# preparedinstruments_0_bechemel_v12_KEYPA.net
KiCad netlist of a schematic drawn in EAGLE
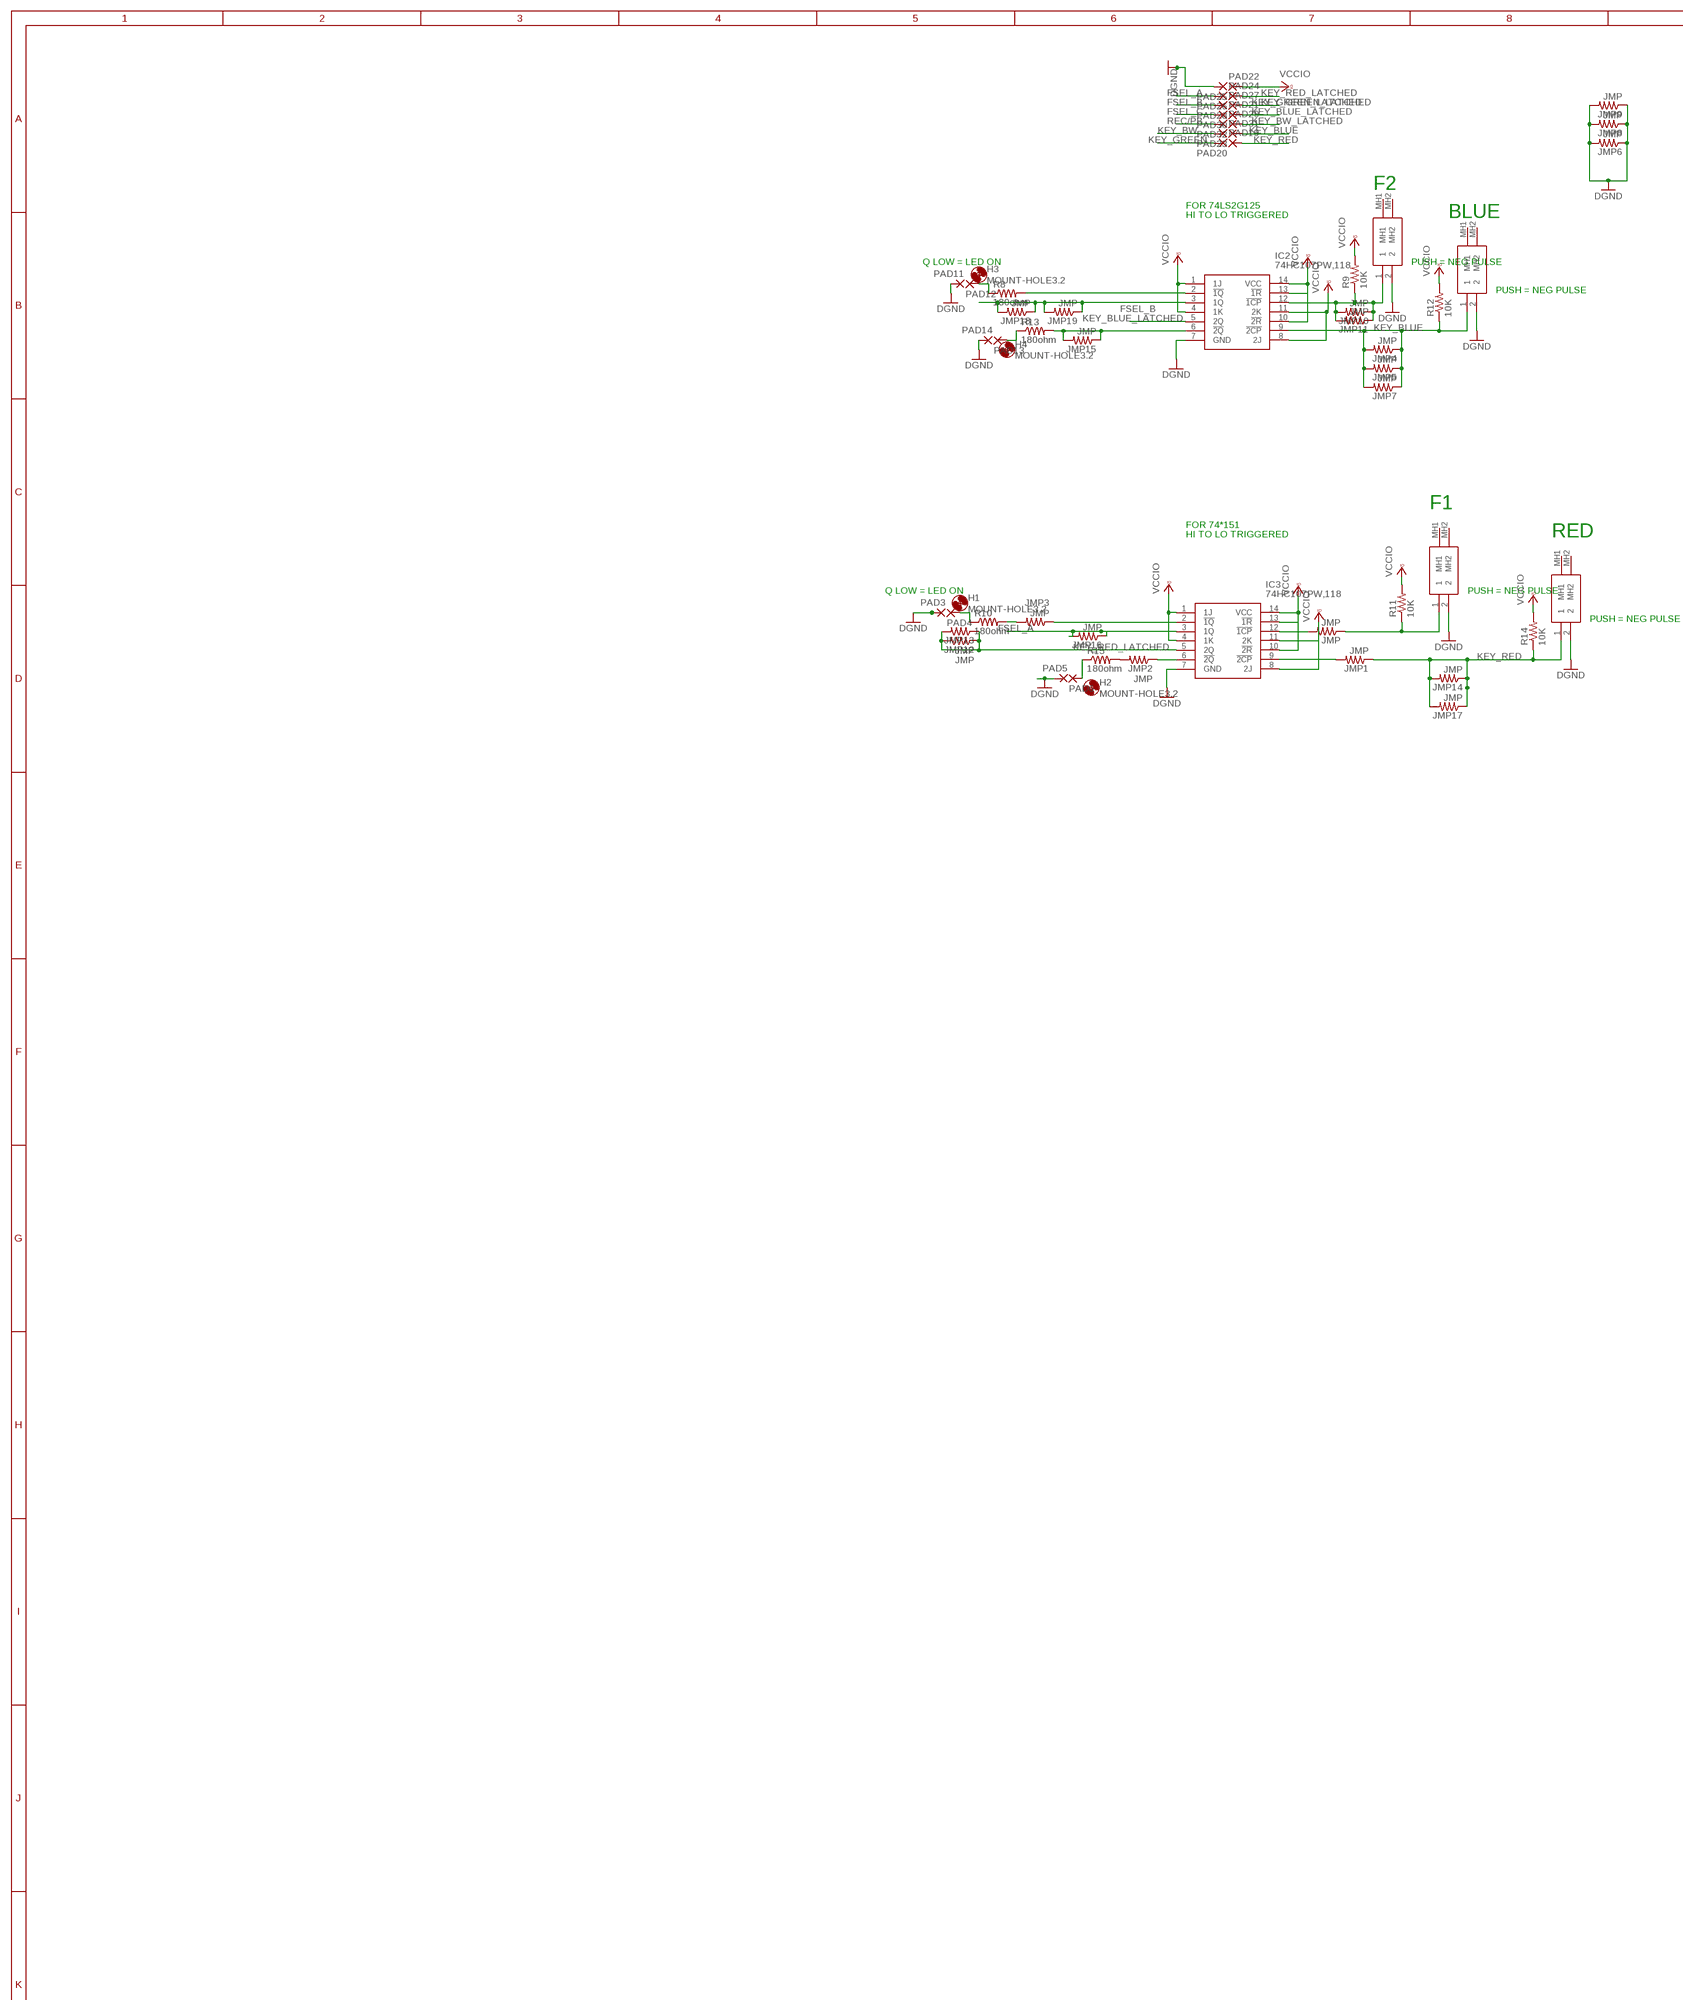
[diagram p0: schematic, sheet 1, part 1 of 3]
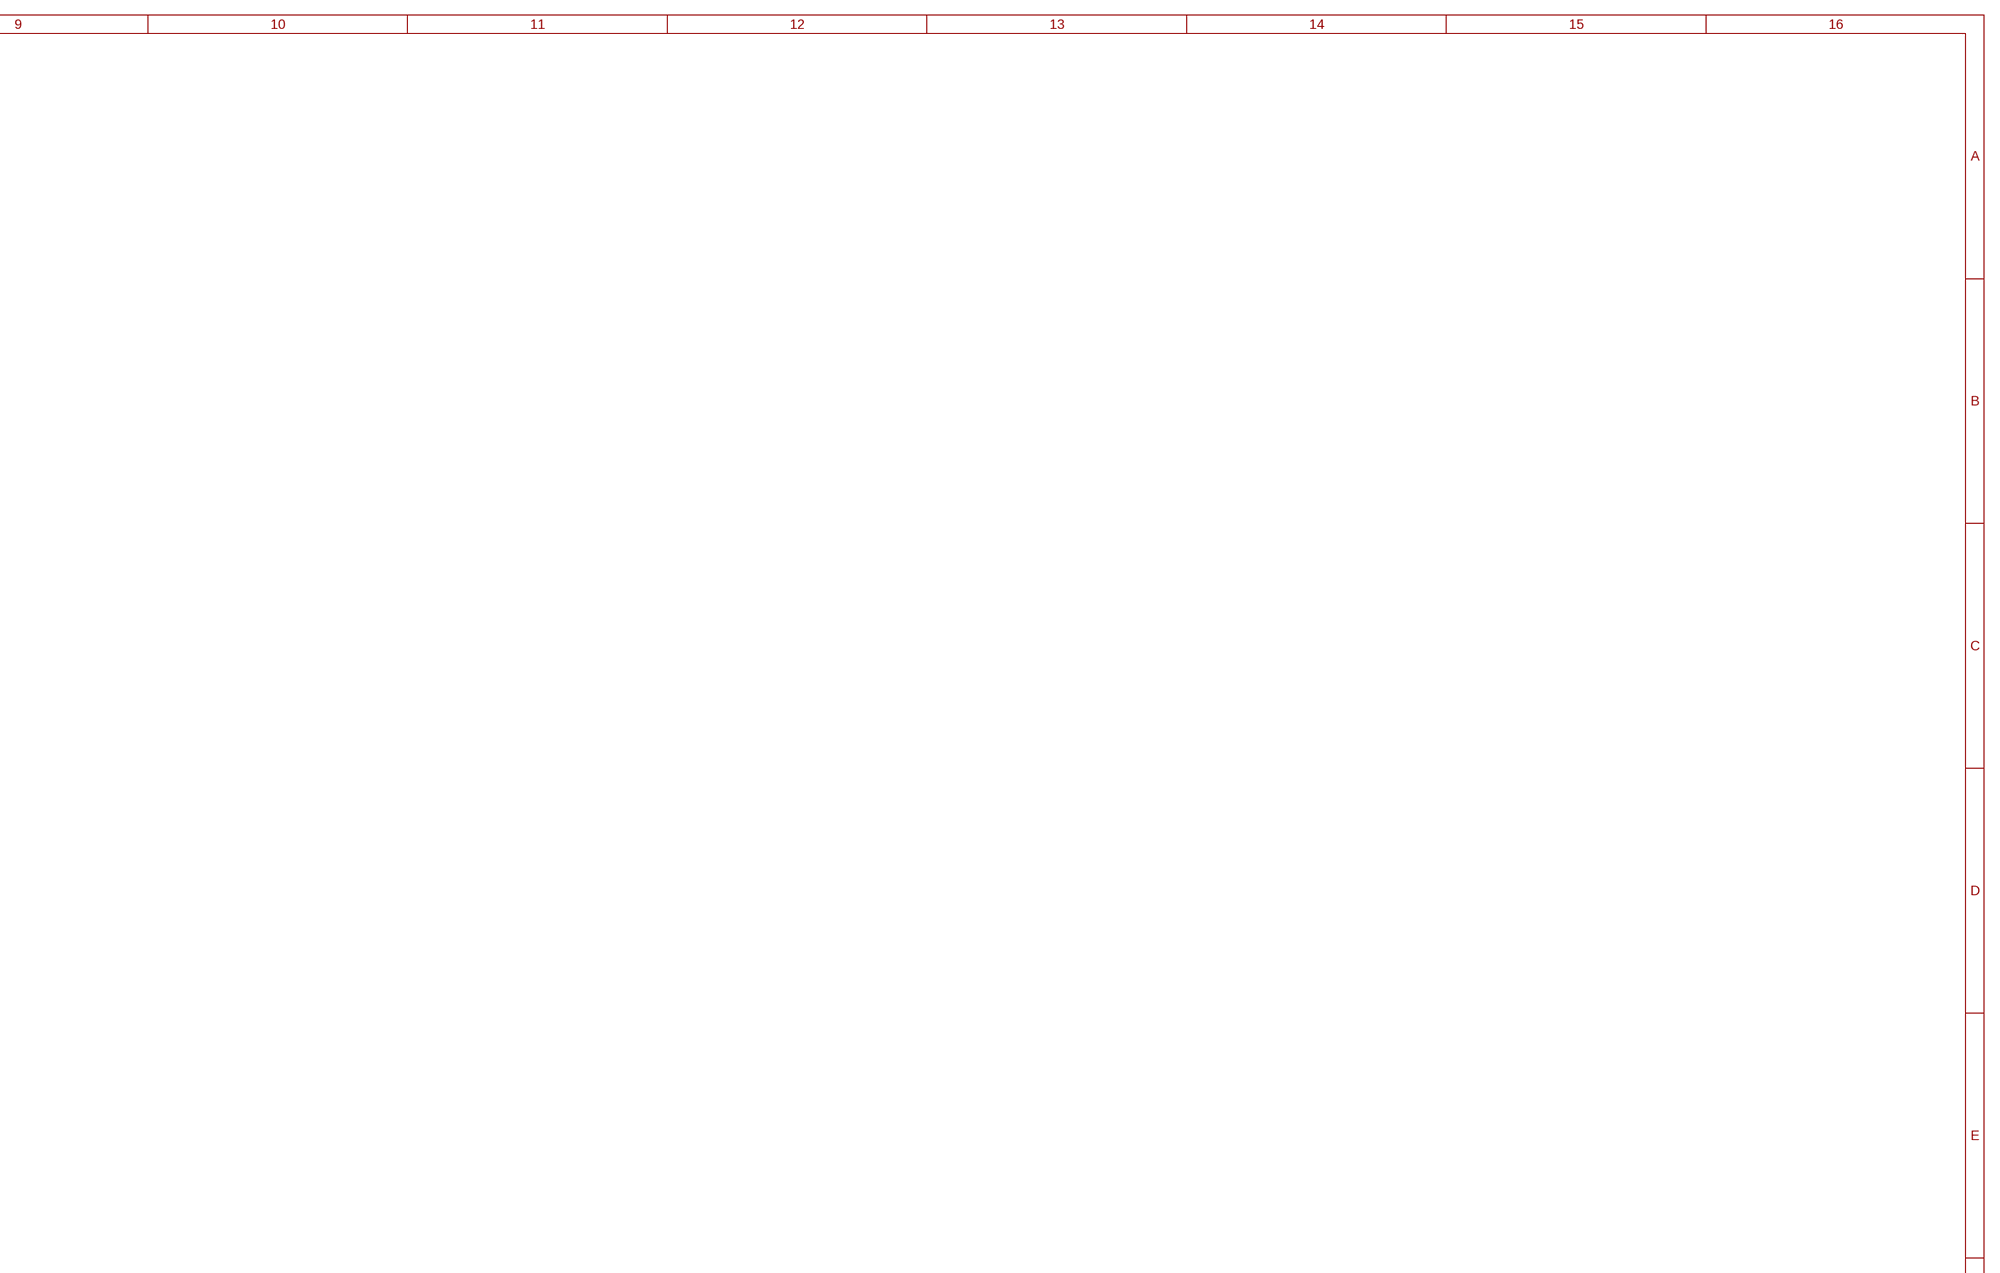
[diagram p1: schematic, sheet 1, part 2 of 3]
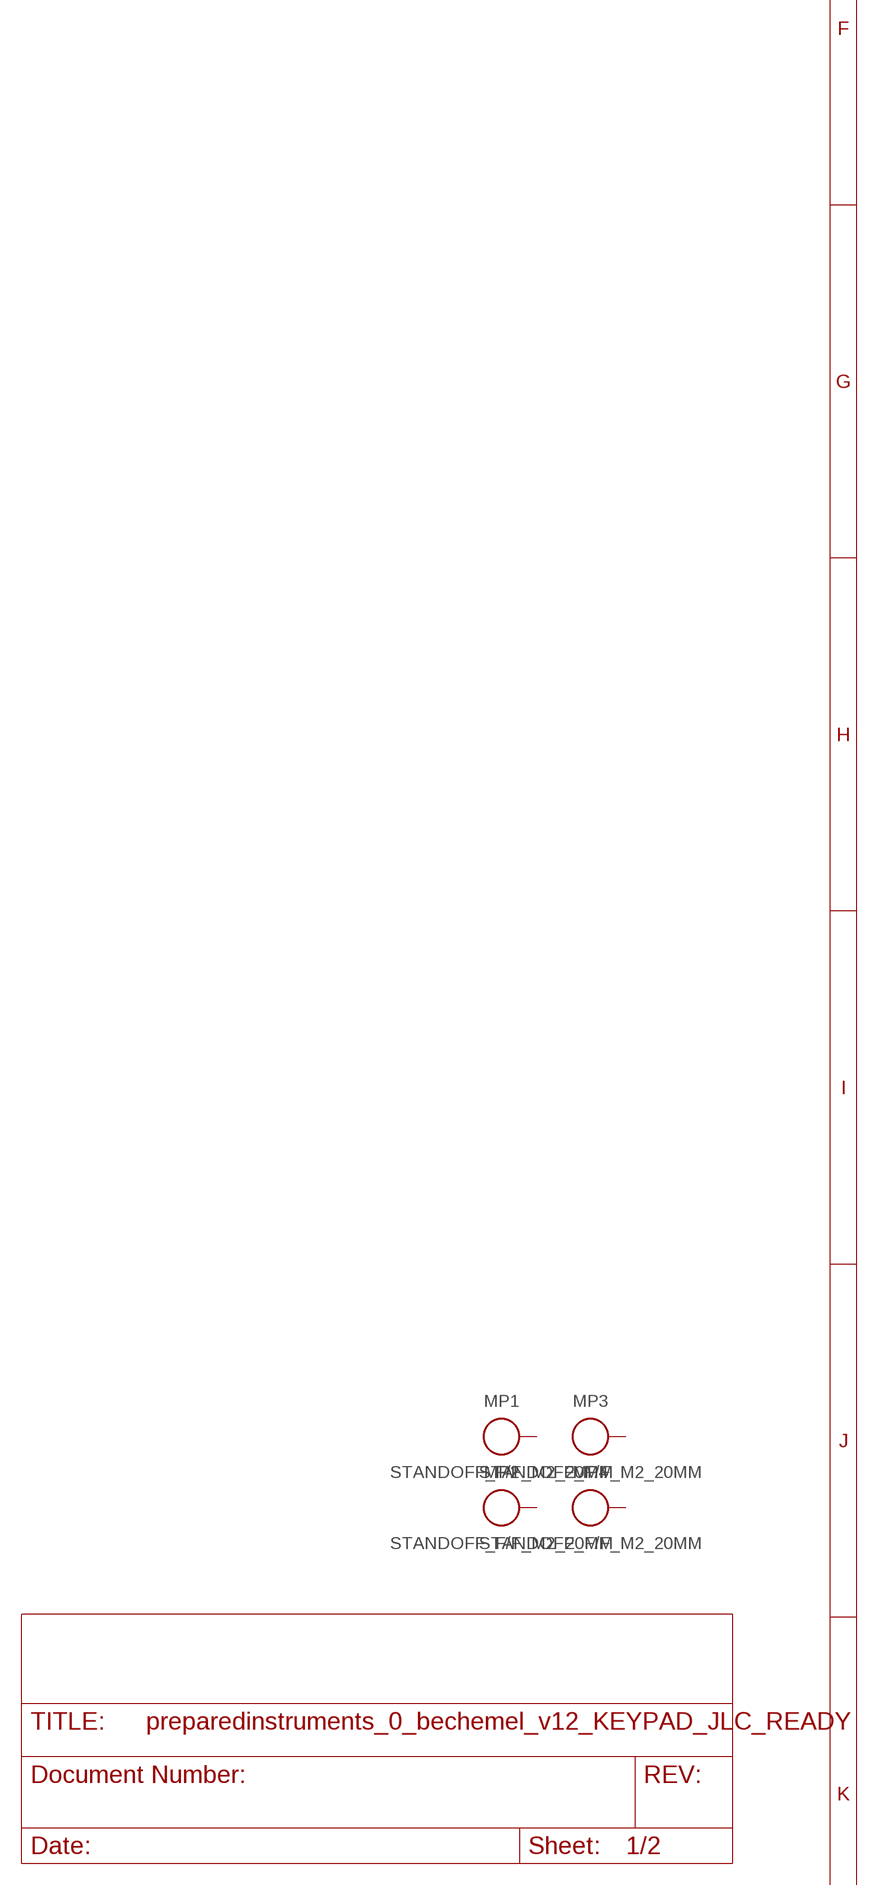
[diagram p2: schematic, sheet 1, part 3 of 3]
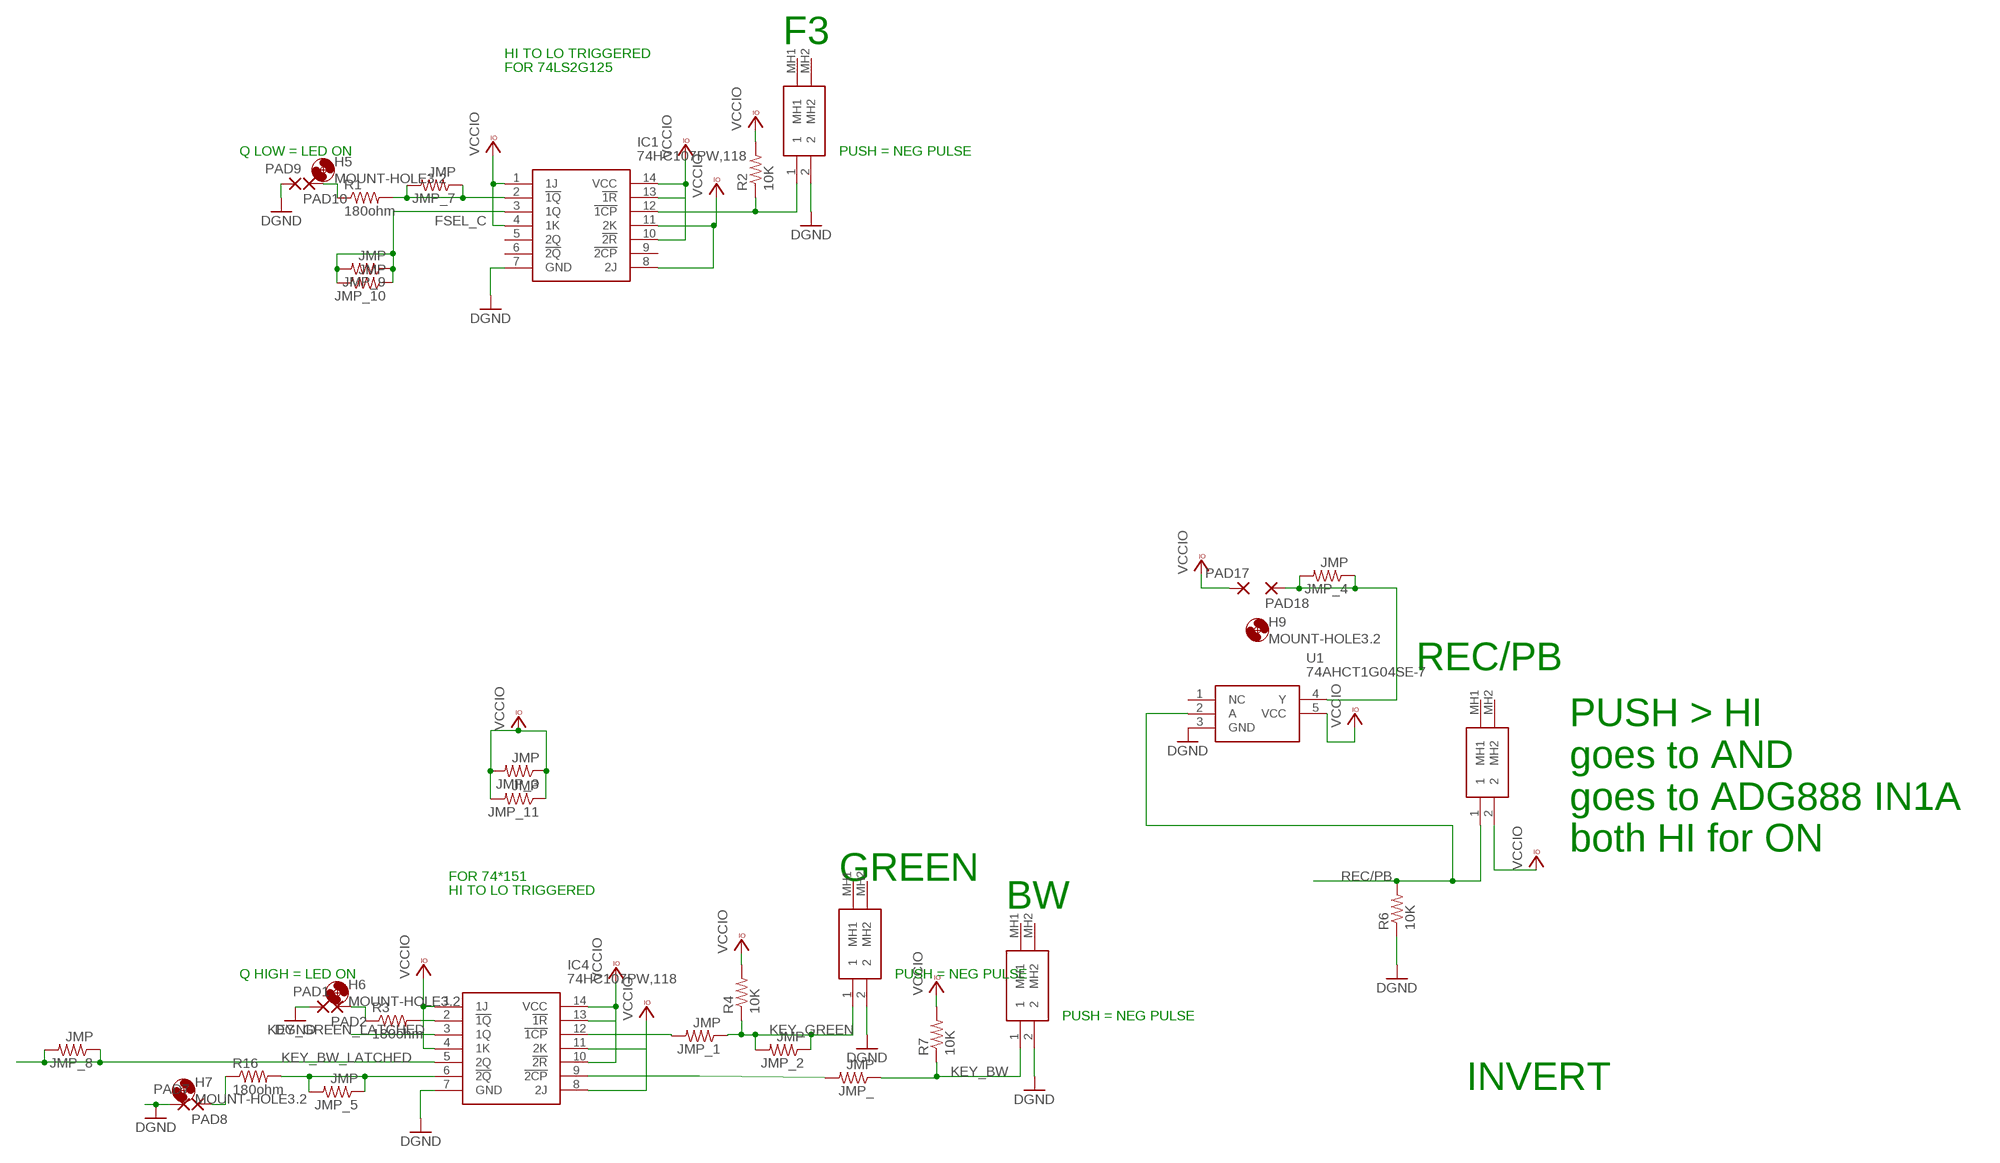
[diagram p3: schematic, sheet 2]

(export (version "E")
  (design (tool "Eeschema 10.0.6"))
  (components
    (comp (ref "H5")
      (value "MOUNT-HOLE3.2")
      (footprint "eagle-import:3,2")
      (libsource (lib "eagle-import") (part "MOUNT-HOLE3.2"))
    )
    (comp (ref "H6")
      (value "MOUNT-HOLE3.2")
      (footprint "eagle-import:3,2")
      (libsource (lib "eagle-import") (part "MOUNT-HOLE3.2"))
    )
    (comp (ref "H7")
      (value "MOUNT-HOLE3.2")
      (footprint "eagle-import:3,2")
      (libsource (lib "eagle-import") (part "MOUNT-HOLE3.2"))
    )
    (comp (ref "H9")
      (value "MOUNT-HOLE3.2")
      (footprint "eagle-import:3,2")
      (libsource (lib "eagle-import") (part "MOUNT-HOLE3.2"))
    )
    (comp (ref "IC1")
      (value "74HC107PW,118")
      (footprint "eagle-import:SOP65P640X110-14N")
      (fields (field (name "MOUSER_PART_NUMBER") "771-HC107PW118"))
      (libsource (lib "eagle-import") (part "74HC107PW,118"))
    )
    (comp (ref "IC4")
      (value "74HC107PW,118")
      (footprint "eagle-import:SOP65P640X110-14N")
      (fields (field (name "MOUSER_PART_NUMBER") "771-HC107PW118"))
      (libsource (lib "eagle-import") (part "74HC107PW,118"))
    )
    (comp (ref "JMP_")
      (value "JMP")
      (footprint "eagle-import:R0805")
      (libsource (lib "eagle-import") (part "R-US_R0805"))
    )
    (comp (ref "JMP_1")
      (value "JMP")
      (footprint "eagle-import:R0805")
      (libsource (lib "eagle-import") (part "R-US_R0805"))
    )
    (comp (ref "JMP_2")
      (value "JMP")
      (footprint "eagle-import:R0805")
      (libsource (lib "eagle-import") (part "R-US_R0805"))
    )
    (comp (ref "JMP_3")
      (value "JMP")
      (footprint "eagle-import:R0805")
      (libsource (lib "eagle-import") (part "R-US_R0805"))
    )
    (comp (ref "JMP_4")
      (value "JMP")
      (footprint "eagle-import:R0805")
      (libsource (lib "eagle-import") (part "R-US_R0805"))
    )
    (comp (ref "JMP_5")
      (value "JMP")
      (footprint "eagle-import:R0805")
      (libsource (lib "eagle-import") (part "R-US_R0805"))
    )
    (comp (ref "JMP_7")
      (value "JMP")
      (footprint "eagle-import:R0805")
      (libsource (lib "eagle-import") (part "R-US_R0805"))
    )
    (comp (ref "JMP_8")
      (value "JMP")
      (footprint "eagle-import:R0805")
      (libsource (lib "eagle-import") (part "R-US_R0805"))
    )
    (comp (ref "JMP_9")
      (value "JMP")
      (footprint "eagle-import:R0805")
      (libsource (lib "eagle-import") (part "R-US_R0805"))
    )
    (comp (ref "JMP_10")
      (value "JMP")
      (footprint "eagle-import:R0805")
      (libsource (lib "eagle-import") (part "R-US_R0805"))
    )
    (comp (ref "JMP_11")
      (value "JMP")
      (footprint "eagle-import:R0805")
      (libsource (lib "eagle-import") (part "R-US_R0805"))
    )
    (comp (ref "PAD1")
      (value "SMD2")
      (footprint "eagle-import:SMD1,27-2,54")
      (libsource (lib "eagle-import") (part "SMD2"))
    )
    (comp (ref "PAD2")
      (value "SMD2")
      (footprint "eagle-import:SMD1,27-2,54")
      (libsource (lib "eagle-import") (part "SMD2"))
    )
    (comp (ref "PAD7")
      (value "SMD2")
      (footprint "eagle-import:SMD1,27-2,54")
      (libsource (lib "eagle-import") (part "SMD2"))
    )
    (comp (ref "PAD8")
      (value "SMD2")
      (footprint "eagle-import:SMD1,27-2,54")
      (libsource (lib "eagle-import") (part "SMD2"))
    )
    (comp (ref "PAD9")
      (value "SMD2")
      (footprint "eagle-import:SMD1,27-2,54")
      (libsource (lib "eagle-import") (part "SMD2"))
    )
    (comp (ref "PAD10")
      (value "SMD2")
      (footprint "eagle-import:SMD1,27-2,54")
      (libsource (lib "eagle-import") (part "SMD2"))
    )
    (comp (ref "PAD17")
      (value "SMD2")
      (footprint "eagle-import:SMD1,27-2,54")
      (libsource (lib "eagle-import") (part "SMD2"))
    )
    (comp (ref "PAD18")
      (value "SMD2")
      (footprint "eagle-import:SMD1,27-2,54")
      (libsource (lib "eagle-import") (part "SMD2"))
    )
    (comp (ref "R1")
      (value "180ohm")
      (footprint "eagle-import:R0805")
      (libsource (lib "eagle-import") (part "R-US_R0805"))
    )
    (comp (ref "R2")
      (value "10K")
      (footprint "eagle-import:R0805")
      (libsource (lib "eagle-import") (part "R-US_R0805"))
    )
    (comp (ref "R3")
      (value "180ohm")
      (footprint "eagle-import:R0805")
      (libsource (lib "eagle-import") (part "R-US_R0805"))
    )
    (comp (ref "R4")
      (value "10K")
      (footprint "eagle-import:R0805")
      (libsource (lib "eagle-import") (part "R-US_R0805"))
    )
    (comp (ref "R6")
      (value "10K")
      (footprint "eagle-import:R0805")
      (libsource (lib "eagle-import") (part "R-US_R0805"))
    )
    (comp (ref "R7")
      (value "10K")
      (footprint "eagle-import:R0805")
      (libsource (lib "eagle-import") (part "R-US_R0805"))
    )
    (comp (ref "R16")
      (value "180ohm")
      (footprint "eagle-import:R0805")
      (libsource (lib "eagle-import") (part "R-US_R0805"))
    )
    (comp (ref "S1")
      (value "MX1A-11NW")
      (footprint "eagle-import:MX1A11NW")
      (fields (field (name "MOUSER_PART_NUMBER") "540-MX1A-11NW"))
      (libsource (lib "eagle-import") (part "MX1A-11NW"))
    )
    (comp (ref "S2")
      (value "MX1A-11NW")
      (footprint "eagle-import:MX1A11NW")
      (fields (field (name "MOUSER_PART_NUMBER") "540-MX1A-11NW"))
      (libsource (lib "eagle-import") (part "MX1A-11NW"))
    )
    (comp (ref "S4")
      (value "MX1A-11NW")
      (footprint "eagle-import:MX1A11NW")
      (fields (field (name "MOUSER_PART_NUMBER") "540-MX1A-11NW"))
      (libsource (lib "eagle-import") (part "MX1A-11NW"))
    )
    (comp (ref "S5")
      (value "MX1A-11NW")
      (footprint "eagle-import:MX1A11NW")
      (fields (field (name "MOUSER_PART_NUMBER") "540-MX1A-11NW"))
      (libsource (lib "eagle-import") (part "MX1A-11NW"))
    )
    (comp (ref "U1")
      (value "74AHCT1G04SE-7")
      (footprint "eagle-import:SOT65P210X110-5N")
      (fields (field (name "MOUSER_PART_NUMBER") "621-74AHCT1G04SE-7"))
      (libsource (lib "eagle-import") (part "74AHCT1G04SE-7"))
    )
    (comp (ref "H1")
      (value "MOUNT-HOLE3.2")
      (footprint "eagle-import:3,2")
      (libsource (lib "eagle-import") (part "MOUNT-HOLE3.2"))
    )
    (comp (ref "H2")
      (value "MOUNT-HOLE3.2")
      (footprint "eagle-import:3,2")
      (libsource (lib "eagle-import") (part "MOUNT-HOLE3.2"))
    )
    (comp (ref "H3")
      (value "MOUNT-HOLE3.2")
      (footprint "eagle-import:3,2")
      (libsource (lib "eagle-import") (part "MOUNT-HOLE3.2"))
    )
    (comp (ref "H4")
      (value "MOUNT-HOLE3.2")
      (footprint "eagle-import:3,2")
      (libsource (lib "eagle-import") (part "MOUNT-HOLE3.2"))
    )
    (comp (ref "IC2")
      (value "74HC107PW,118")
      (footprint "eagle-import:SOP65P640X110-14N")
      (fields (field (name "MOUSER_PART_NUMBER") "771-HC107PW118"))
      (libsource (lib "eagle-import") (part "74HC107PW,118"))
    )
    (comp (ref "IC3")
      (value "74HC107PW,118")
      (footprint "eagle-import:SOP65P640X110-14N")
      (fields (field (name "MOUSER_PART_NUMBER") "771-HC107PW118"))
      (libsource (lib "eagle-import") (part "74HC107PW,118"))
    )
    (comp (ref "JMP")
      (value "JMP")
      (footprint "eagle-import:R0805")
      (libsource (lib "eagle-import") (part "R-US_R0805"))
    )
    (comp (ref "JMP1")
      (value "JMP")
      (footprint "eagle-import:R0805")
      (libsource (lib "eagle-import") (part "R-US_R0805"))
    )
    (comp (ref "JMP2")
      (value "JMP")
      (footprint "eagle-import:R0805")
      (libsource (lib "eagle-import") (part "R-US_R0805"))
    )
    (comp (ref "JMP3")
      (value "JMP")
      (footprint "eagle-import:R0805")
      (libsource (lib "eagle-import") (part "R-US_R0805"))
    )
    (comp (ref "JMP4")
      (value "JMP")
      (footprint "eagle-import:R0805")
      (libsource (lib "eagle-import") (part "R-US_R0805"))
    )
    (comp (ref "JMP5")
      (value "JMP")
      (footprint "eagle-import:R0805")
      (libsource (lib "eagle-import") (part "R-US_R0805"))
    )
    (comp (ref "JMP6")
      (value "JMP")
      (footprint "eagle-import:R0805")
      (libsource (lib "eagle-import") (part "R-US_R0805"))
    )
    (comp (ref "JMP7")
      (value "JMP")
      (footprint "eagle-import:R0805")
      (libsource (lib "eagle-import") (part "R-US_R0805"))
    )
    (comp (ref "JMP8")
      (value "JMP")
      (footprint "eagle-import:R0805")
      (libsource (lib "eagle-import") (part "R-US_R0805"))
    )
    (comp (ref "JMP9")
      (value "JMP")
      (footprint "eagle-import:R0805")
      (libsource (lib "eagle-import") (part "R-US_R0805"))
    )
    (comp (ref "JMP10")
      (value "JMP")
      (footprint "eagle-import:R0805")
      (libsource (lib "eagle-import") (part "R-US_R0805"))
    )
    (comp (ref "JMP11")
      (value "JMP")
      (footprint "eagle-import:R0805")
      (libsource (lib "eagle-import") (part "R-US_R0805"))
    )
    (comp (ref "JMP12")
      (value "JMP")
      (footprint "eagle-import:R0805")
      (libsource (lib "eagle-import") (part "R-US_R0805"))
    )
    (comp (ref "JMP13")
      (value "JMP")
      (footprint "eagle-import:R0805")
      (libsource (lib "eagle-import") (part "R-US_R0805"))
    )
    (comp (ref "JMP14")
      (value "JMP")
      (footprint "eagle-import:R0805")
      (libsource (lib "eagle-import") (part "R-US_R0805"))
    )
    (comp (ref "JMP15")
      (value "JMP")
      (footprint "eagle-import:R0805")
      (libsource (lib "eagle-import") (part "R-US_R0805"))
    )
    (comp (ref "JMP16")
      (value "JMP")
      (footprint "eagle-import:R0805")
      (libsource (lib "eagle-import") (part "R-US_R0805"))
    )
    (comp (ref "JMP17")
      (value "JMP")
      (footprint "eagle-import:R0805")
      (libsource (lib "eagle-import") (part "R-US_R0805"))
    )
    (comp (ref "JMP18")
      (value "JMP")
      (footprint "eagle-import:R0805")
      (libsource (lib "eagle-import") (part "R-US_R0805"))
    )
    (comp (ref "JMP19")
      (value "JMP")
      (footprint "eagle-import:R0805")
      (libsource (lib "eagle-import") (part "R-US_R0805"))
    )
    (comp (ref "MP1")
      (value "STANDOFF_F/F_M2_20MM")
      (footprint "eagle-import:STANDOFF_HEX_FEMALE_400X2000_M2X0.4_MTGP600H220")
      (libsource (lib "eagle-import") (part "STANDOFF_F/FM2_20MM_"))
    )
    (comp (ref "MP2")
      (value "STANDOFF_F/F_M2_20MM")
      (footprint "eagle-import:STANDOFF_HEX_FEMALE_400X2000_M2X0.4_MTGP600H220")
      (libsource (lib "eagle-import") (part "STANDOFF_F/FM2_20MM_"))
    )
    (comp (ref "MP3")
      (value "STANDOFF_F/F_M2_20MM")
      (footprint "eagle-import:STANDOFF_HEX_FEMALE_400X2000_M2X0.4_MTGP600H220")
      (libsource (lib "eagle-import") (part "STANDOFF_F/FM2_20MM_"))
    )
    (comp (ref "MP4")
      (value "STANDOFF_F/F_M2_20MM")
      (footprint "eagle-import:STANDOFF_HEX_FEMALE_400X2000_M2X0.4_MTGP600H220")
      (libsource (lib "eagle-import") (part "STANDOFF_F/FM2_20MM_"))
    )
    (comp (ref "PAD3")
      (value "SMD2")
      (footprint "eagle-import:SMD1,27-2,54")
      (libsource (lib "eagle-import") (part "SMD2"))
    )
    (comp (ref "PAD4")
      (value "SMD2")
      (footprint "eagle-import:SMD1,27-2,54")
      (libsource (lib "eagle-import") (part "SMD2"))
    )
    (comp (ref "PAD5")
      (value "SMD2")
      (footprint "eagle-import:SMD1,27-2,54")
      (libsource (lib "eagle-import") (part "SMD2"))
    )
    (comp (ref "PAD6")
      (value "SMD2")
      (footprint "eagle-import:SMD1,27-2,54")
      (libsource (lib "eagle-import") (part "SMD2"))
    )
    (comp (ref "PAD11")
      (value "SMD2")
      (footprint "eagle-import:SMD1,27-2,54")
      (libsource (lib "eagle-import") (part "SMD2"))
    )
    (comp (ref "PAD12")
      (value "SMD2")
      (footprint "eagle-import:SMD1,27-2,54")
      (libsource (lib "eagle-import") (part "SMD2"))
    )
    (comp (ref "PAD13")
      (value "SMD2")
      (footprint "eagle-import:SMD1,27-2,54")
      (libsource (lib "eagle-import") (part "SMD2"))
    )
    (comp (ref "PAD14")
      (value "SMD2")
      (footprint "eagle-import:SMD1,27-2,54")
      (libsource (lib "eagle-import") (part "SMD2"))
    )
    (comp (ref "PAD19")
      (value "SMD2")
      (footprint "eagle-import:SMD1,27-2,54")
      (libsource (lib "eagle-import") (part "SMD2"))
    )
    (comp (ref "PAD20")
      (value "SMD2")
      (footprint "eagle-import:SMD1,27-2,54")
      (libsource (lib "eagle-import") (part "SMD2"))
    )
    (comp (ref "PAD21")
      (value "SMD2")
      (footprint "eagle-import:SMD1,27-2,54")
      (libsource (lib "eagle-import") (part "SMD2"))
    )
    (comp (ref "PAD22")
      (value "SMD2")
      (footprint "eagle-import:SMD1,27-2,54")
      (libsource (lib "eagle-import") (part "SMD2"))
    )
    (comp (ref "PAD23")
      (value "SMD2")
      (footprint "eagle-import:SMD1,27-2,54")
      (libsource (lib "eagle-import") (part "SMD2"))
    )
    (comp (ref "PAD24")
      (value "SMD2")
      (footprint "eagle-import:SMD1,27-2,54")
      (libsource (lib "eagle-import") (part "SMD2"))
    )
    (comp (ref "PAD25")
      (value "SMD2")
      (footprint "eagle-import:SMD1,27-2,54")
      (libsource (lib "eagle-import") (part "SMD2"))
    )
    (comp (ref "PAD26")
      (value "SMD2")
      (footprint "eagle-import:SMD1,27-2,54")
      (libsource (lib "eagle-import") (part "SMD2"))
    )
    (comp (ref "PAD27")
      (value "SMD2")
      (footprint "eagle-import:SMD1,27-2,54")
      (libsource (lib "eagle-import") (part "SMD2"))
    )
    (comp (ref "PAD28")
      (value "SMD2")
      (footprint "eagle-import:SMD1,27-2,54")
      (libsource (lib "eagle-import") (part "SMD2"))
    )
    (comp (ref "PAD29")
      (value "SMD2")
      (footprint "eagle-import:SMD1,27-2,54")
      (libsource (lib "eagle-import") (part "SMD2"))
    )
    (comp (ref "PAD30")
      (value "SMD2")
      (footprint "eagle-import:SMD1,27-2,54")
      (libsource (lib "eagle-import") (part "SMD2"))
    )
    (comp (ref "PAD31")
      (value "SMD2")
      (footprint "eagle-import:SMD1,27-2,54")
      (libsource (lib "eagle-import") (part "SMD2"))
    )
    (comp (ref "PAD32")
      (value "SMD2")
      (footprint "eagle-import:SMD1,27-2,54")
      (libsource (lib "eagle-import") (part "SMD2"))
    )
    (comp (ref "R8")
      (value "180ohm")
      (footprint "eagle-import:R0805")
      (libsource (lib "eagle-import") (part "R-US_R0805"))
    )
    (comp (ref "R9")
      (value "10K")
      (footprint "eagle-import:R0805")
      (libsource (lib "eagle-import") (part "R-US_R0805"))
    )
    (comp (ref "R10")
      (value "180ohm")
      (footprint "eagle-import:R0805")
      (libsource (lib "eagle-import") (part "R-US_R0805"))
    )
    (comp (ref "R11")
      (value "10K")
      (footprint "eagle-import:R0805")
      (libsource (lib "eagle-import") (part "R-US_R0805"))
    )
    (comp (ref "R12")
      (value "10K")
      (footprint "eagle-import:R0805")
      (libsource (lib "eagle-import") (part "R-US_R0805"))
    )
    (comp (ref "R13")
      (value "180ohm")
      (footprint "eagle-import:R0805")
      (libsource (lib "eagle-import") (part "R-US_R0805"))
    )
    (comp (ref "R14")
      (value "10K")
      (footprint "eagle-import:R0805")
      (libsource (lib "eagle-import") (part "R-US_R0805"))
    )
    (comp (ref "R15")
      (value "180ohm")
      (footprint "eagle-import:R0805")
      (libsource (lib "eagle-import") (part "R-US_R0805"))
    )
    (comp (ref "S6")
      (value "MX1A-11NW")
      (footprint "eagle-import:MX1A11NW")
      (fields (field (name "MOUSER_PART_NUMBER") "540-MX1A-11NW"))
      (libsource (lib "eagle-import") (part "MX1A-11NW"))
    )
    (comp (ref "S7")
      (value "MX1A-11NW")
      (footprint "eagle-import:MX1A11NW")
      (fields (field (name "MOUSER_PART_NUMBER") "540-MX1A-11NW"))
      (libsource (lib "eagle-import") (part "MX1A-11NW"))
    )
    (comp (ref "S8")
      (value "MX1A-11NW")
      (footprint "eagle-import:MX1A11NW")
      (fields (field (name "MOUSER_PART_NUMBER") "540-MX1A-11NW"))
      (libsource (lib "eagle-import") (part "MX1A-11NW"))
    )
    (comp (ref "S9")
      (value "MX1A-11NW")
      (footprint "eagle-import:MX1A11NW")
      (fields (field (name "MOUSER_PART_NUMBER") "540-MX1A-11NW"))
      (libsource (lib "eagle-import") (part "MX1A-11NW"))
    )
  )
  (nets
    (net (code "1") (name "DGND") (class "Default")
      (node (ref "IC1") (pin "7") (pinfunction "GND_7") (pintype "bidirectional"))
      (node (ref "IC2") (pin "7") (pinfunction "GND_7") (pintype "bidirectional"))
      (node (ref "IC3") (pin "7") (pinfunction "GND_7") (pintype "bidirectional"))
      (node (ref "IC4") (pin "7") (pinfunction "GND_7") (pintype "bidirectional"))
      (node (ref "JMP6") (pin "1") (pinfunction "1_1") (pintype "passive"))
      (node (ref "JMP6") (pin "2") (pinfunction "2_2") (pintype "passive"))
      (node (ref "JMP8") (pin "1") (pinfunction "1_1") (pintype "passive"))
      (node (ref "JMP8") (pin "2") (pinfunction "2_2") (pintype "passive"))
      (node (ref "JMP9") (pin "1") (pinfunction "1_1") (pintype "passive"))
      (node (ref "JMP9") (pin "2") (pinfunction "2_2") (pintype "passive"))
      (node (ref "PAD1") (pin "1") (pinfunction "P_1") (pintype "passive"))
      (node (ref "PAD11") (pin "1") (pinfunction "P_1") (pintype "passive"))
      (node (ref "PAD14") (pin "1") (pinfunction "P_1") (pintype "passive"))
      (node (ref "PAD25") (pin "1") (pinfunction "P_1") (pintype "passive"))
      (node (ref "PAD3") (pin "1") (pinfunction "P_1") (pintype "passive"))
      (node (ref "PAD5") (pin "1") (pinfunction "P_1") (pintype "passive"))
      (node (ref "PAD7") (pin "1") (pinfunction "P_1") (pintype "passive"))
      (node (ref "PAD9") (pin "1") (pinfunction "P_1") (pintype "passive"))
      (node (ref "R6") (pin "1") (pinfunction "1_1") (pintype "passive"))
      (node (ref "S1") (pin "2") (pinfunction "2_2") (pintype "bidirectional"))
      (node (ref "S2") (pin "2") (pinfunction "2_2") (pintype "bidirectional"))
      (node (ref "S4") (pin "2") (pinfunction "2_2") (pintype "bidirectional"))
      (node (ref "S6") (pin "2") (pinfunction "2_2") (pintype "bidirectional"))
      (node (ref "S7") (pin "2") (pinfunction "2_2") (pintype "bidirectional"))
      (node (ref "S8") (pin "2") (pinfunction "2_2") (pintype "bidirectional"))
      (node (ref "S9") (pin "2") (pinfunction "2_2") (pintype "bidirectional"))
      (node (ref "U1") (pin "3") (pinfunction "GND_3") (pintype "bidirectional"))
    )
    (net (code "2") (name "FSEL_A") (class "Default")
      (node (ref "IC3") (pin "3") (pinfunction "1Q_3") (pintype "bidirectional"))
      (node (ref "JMP16") (pin "1") (pinfunction "1_1") (pintype "passive"))
      (node (ref "JMP16") (pin "2") (pinfunction "2_2") (pintype "passive"))
      (node (ref "PAD26") (pin "1") (pinfunction "P_1") (pintype "passive"))
    )
    (net (code "3") (name "FSEL_B") (class "Default")
      (node (ref "IC2") (pin "3") (pinfunction "1Q_3") (pintype "bidirectional"))
      (node (ref "JMP18") (pin "1") (pinfunction "1_1") (pintype "passive"))
      (node (ref "JMP18") (pin "2") (pinfunction "2_2") (pintype "passive"))
      (node (ref "JMP19") (pin "1") (pinfunction "1_1") (pintype "passive"))
      (node (ref "JMP19") (pin "2") (pinfunction "2_2") (pintype "passive"))
      (node (ref "PAD28") (pin "1") (pinfunction "P_1") (pintype "passive"))
    )
    (net (code "4") (name "FSEL_C") (class "Default")
      (node (ref "IC1") (pin "3") (pinfunction "1Q_3") (pintype "bidirectional"))
      (node (ref "JMP_10") (pin "1") (pinfunction "1_1") (pintype "passive"))
      (node (ref "JMP_10") (pin "2") (pinfunction "2_2") (pintype "passive"))
      (node (ref "JMP_9") (pin "1") (pinfunction "1_1") (pintype "passive"))
      (node (ref "JMP_9") (pin "2") (pinfunction "2_2") (pintype "passive"))
      (node (ref "PAD30") (pin "1") (pinfunction "P_1") (pintype "passive"))
    )
    (net (code "5") (name "KEY_BLUE") (class "Default")
      (node (ref "IC2") (pin "9") (pinfunction "~{2CP}_9") (pintype "bidirectional"))
      (node (ref "JMP4") (pin "1") (pinfunction "1_1") (pintype "passive"))
      (node (ref "JMP4") (pin "2") (pinfunction "2_2") (pintype "passive"))
      (node (ref "JMP5") (pin "1") (pinfunction "1_1") (pintype "passive"))
      (node (ref "JMP5") (pin "2") (pinfunction "2_2") (pintype "passive"))
      (node (ref "JMP7") (pin "1") (pinfunction "1_1") (pintype "passive"))
      (node (ref "JMP7") (pin "2") (pinfunction "2_2") (pintype "passive"))
      (node (ref "PAD31") (pin "1") (pinfunction "P_1") (pintype "passive"))
      (node (ref "R12") (pin "1") (pinfunction "1_1") (pintype "passive"))
      (node (ref "S8") (pin "1") (pinfunction "1_1") (pintype "bidirectional"))
    )
    (net (code "6") (name "KEY_BLUE_LATCHED") (class "Default")
      (node (ref "IC2") (pin "5") (pinfunction "2Q_5") (pintype "bidirectional"))
      (node (ref "PAD21") (pin "1") (pinfunction "P_1") (pintype "passive"))
    )
    (net (code "7") (name "KEY_BW") (class "Default")
      (node (ref "JMP_") (pin "1") (pinfunction "1_1") (pintype "passive"))
      (node (ref "PAD23") (pin "1") (pinfunction "P_1") (pintype "passive"))
      (node (ref "R7") (pin "1") (pinfunction "1_1") (pintype "passive"))
      (node (ref "S4") (pin "1") (pinfunction "1_1") (pintype "bidirectional"))
    )
    (net (code "8") (name "KEY_BW_LATCHED") (class "Default")
      (node (ref "IC4") (pin "5") (pinfunction "2Q_5") (pintype "bidirectional"))
      (node (ref "JMP_8") (pin "1") (pinfunction "1_1") (pintype "passive"))
      (node (ref "JMP_8") (pin "2") (pinfunction "2_2") (pintype "passive"))
      (node (ref "PAD29") (pin "1") (pinfunction "P_1") (pintype "passive"))
    )
    (net (code "9") (name "KEY_GREEN") (class "Default")
      (node (ref "JMP_1") (pin "1") (pinfunction "1_1") (pintype "passive"))
      (node (ref "JMP_2") (pin "1") (pinfunction "1_1") (pintype "passive"))
      (node (ref "JMP_2") (pin "2") (pinfunction "2_2") (pintype "passive"))
      (node (ref "PAD20") (pin "1") (pinfunction "P_1") (pintype "passive"))
      (node (ref "R4") (pin "1") (pinfunction "1_1") (pintype "passive"))
      (node (ref "S2") (pin "1") (pinfunction "1_1") (pintype "bidirectional"))
    )
    (net (code "10") (name "KEY_GREEN_LATCHED") (class "Default")
      (node (ref "IC4") (pin "3") (pinfunction "1Q_3") (pintype "bidirectional"))
      (node (ref "PAD27") (pin "1") (pinfunction "P_1") (pintype "passive"))
    )
    (net (code "11") (name "KEY_RED") (class "Default")
      (node (ref "JMP1") (pin "1") (pinfunction "1_1") (pintype "passive"))
      (node (ref "JMP14") (pin "1") (pinfunction "1_1") (pintype "passive"))
      (node (ref "JMP14") (pin "2") (pinfunction "2_2") (pintype "passive"))
      (node (ref "JMP17") (pin "1") (pinfunction "1_1") (pintype "passive"))
      (node (ref "JMP17") (pin "2") (pinfunction "2_2") (pintype "passive"))
      (node (ref "PAD19") (pin "1") (pinfunction "P_1") (pintype "passive"))
      (node (ref "R14") (pin "1") (pinfunction "1_1") (pintype "passive"))
      (node (ref "S9") (pin "1") (pinfunction "1_1") (pintype "bidirectional"))
    )
    (net (code "12") (name "KEY_RED_LATCHED") (class "Default")
      (node (ref "IC3") (pin "5") (pinfunction "2Q_5") (pintype "bidirectional"))
      (node (ref "JMP12") (pin "1") (pinfunction "1_1") (pintype "passive"))
      (node (ref "JMP12") (pin "2") (pinfunction "2_2") (pintype "passive"))
      (node (ref "JMP13") (pin "1") (pinfunction "1_1") (pintype "passive"))
      (node (ref "JMP13") (pin "2") (pinfunction "2_2") (pintype "passive"))
      (node (ref "PAD24") (pin "1") (pinfunction "P_1") (pintype "passive"))
    )
    (net (code "13") (name "Net-(IC1-~{1CP})") (class "Default")
      (node (ref "IC1") (pin "12") (pinfunction "~{1CP}_12") (pintype "bidirectional"))
      (node (ref "R2") (pin "1") (pinfunction "1_1") (pintype "passive"))
      (node (ref "S1") (pin "1") (pinfunction "1_1") (pintype "bidirectional"))
    )
    (net (code "14") (name "Net-(IC1-~{1Q})") (class "Default")
      (node (ref "IC1") (pin "2") (pinfunction "~{1Q}_2") (pintype "bidirectional"))
      (node (ref "JMP_7") (pin "1") (pinfunction "1_1") (pintype "passive"))
      (node (ref "JMP_7") (pin "2") (pinfunction "2_2") (pintype "passive"))
      (node (ref "R1") (pin "2") (pinfunction "2_2") (pintype "passive"))
    )
    (net (code "15") (name "Net-(IC2-~{1CP})") (class "Default")
      (node (ref "IC2") (pin "12") (pinfunction "~{1CP}_12") (pintype "bidirectional"))
      (node (ref "JMP10") (pin "1") (pinfunction "1_1") (pintype "passive"))
      (node (ref "JMP10") (pin "2") (pinfunction "2_2") (pintype "passive"))
      (node (ref "JMP11") (pin "1") (pinfunction "1_1") (pintype "passive"))
      (node (ref "JMP11") (pin "2") (pinfunction "2_2") (pintype "passive"))
      (node (ref "R9") (pin "1") (pinfunction "1_1") (pintype "passive"))
      (node (ref "S6") (pin "1") (pinfunction "1_1") (pintype "bidirectional"))
    )
    (net (code "16") (name "Net-(IC2-~{1Q})") (class "Default")
      (node (ref "IC2") (pin "2") (pinfunction "~{1Q}_2") (pintype "bidirectional"))
      (node (ref "R8") (pin "2") (pinfunction "2_2") (pintype "passive"))
    )
    (net (code "17") (name "Net-(IC2-~{2Q})") (class "Default")
      (node (ref "IC2") (pin "6") (pinfunction "~{2Q}_6") (pintype "bidirectional"))
      (node (ref "JMP15") (pin "1") (pinfunction "1_1") (pintype "passive"))
      (node (ref "JMP15") (pin "2") (pinfunction "2_2") (pintype "passive"))
      (node (ref "R13") (pin "2") (pinfunction "2_2") (pintype "passive"))
    )
    (net (code "18") (name "Net-(IC3-~{1CP})") (class "Default")
      (node (ref "IC3") (pin "12") (pinfunction "~{1CP}_12") (pintype "bidirectional"))
      (node (ref "JMP") (pin "2") (pinfunction "2_2") (pintype "passive"))
    )
    (net (code "19") (name "Net-(IC3-~{1Q})") (class "Default")
      (node (ref "IC3") (pin "2") (pinfunction "~{1Q}_2") (pintype "bidirectional"))
      (node (ref "JMP3") (pin "1") (pinfunction "1_1") (pintype "passive"))
    )
    (net (code "20") (name "Net-(IC3-~{2CP})") (class "Default")
      (node (ref "IC3") (pin "9") (pinfunction "~{2CP}_9") (pintype "bidirectional"))
      (node (ref "JMP1") (pin "2") (pinfunction "2_2") (pintype "passive"))
    )
    (net (code "21") (name "Net-(IC3-~{2Q})") (class "Default")
      (node (ref "IC3") (pin "6") (pinfunction "~{2Q}_6") (pintype "bidirectional"))
      (node (ref "JMP2") (pin "1") (pinfunction "1_1") (pintype "passive"))
    )
    (net (code "22") (name "Net-(IC4-~{1CP})") (class "Default")
      (node (ref "IC4") (pin "12") (pinfunction "~{1CP}_12") (pintype "bidirectional"))
      (node (ref "JMP_1") (pin "2") (pinfunction "2_2") (pintype "passive"))
    )
    (net (code "23") (name "Net-(IC4-~{1Q})") (class "Default")
      (node (ref "IC4") (pin "2") (pinfunction "~{1Q}_2") (pintype "bidirectional"))
      (node (ref "R3") (pin "2") (pinfunction "2_2") (pintype "passive"))
    )
    (net (code "24") (name "Net-(IC4-~{2CP})") (class "Default")
      (node (ref "IC4") (pin "9") (pinfunction "~{2CP}_9") (pintype "bidirectional"))
      (node (ref "JMP_") (pin "2") (pinfunction "2_2") (pintype "passive"))
    )
    (net (code "25") (name "Net-(IC4-~{2Q})") (class "Default")
      (node (ref "IC4") (pin "6") (pinfunction "~{2Q}_6") (pintype "bidirectional"))
      (node (ref "JMP_5") (pin "1") (pinfunction "1_1") (pintype "passive"))
      (node (ref "JMP_5") (pin "2") (pinfunction "2_2") (pintype "passive"))
      (node (ref "R16") (pin "2") (pinfunction "2_2") (pintype "passive"))
    )
    (net (code "26") (name "Net-(JMP-Pad1)") (class "Default")
      (node (ref "JMP") (pin "1") (pinfunction "1_1") (pintype "passive"))
      (node (ref "R11") (pin "1") (pinfunction "1_1") (pintype "passive"))
      (node (ref "S7") (pin "1") (pinfunction "1_1") (pintype "bidirectional"))
    )
    (net (code "27") (name "Net-(JMP2-Pad2)") (class "Default")
      (node (ref "JMP2") (pin "2") (pinfunction "2_2") (pintype "passive"))
      (node (ref "R15") (pin "2") (pinfunction "2_2") (pintype "passive"))
    )
    (net (code "28") (name "Net-(JMP3-Pad2)") (class "Default")
      (node (ref "JMP3") (pin "2") (pinfunction "2_2") (pintype "passive"))
      (node (ref "R10") (pin "2") (pinfunction "2_2") (pintype "passive"))
    )
    (net (code "29") (name "Net-(PAD2-P)") (class "Default")
      (node (ref "PAD2") (pin "1") (pinfunction "P_1") (pintype "passive"))
      (node (ref "R3") (pin "1") (pinfunction "1_1") (pintype "passive"))
    )
    (net (code "30") (name "Net-(PAD4-P)") (class "Default")
      (node (ref "PAD4") (pin "1") (pinfunction "P_1") (pintype "passive"))
      (node (ref "R10") (pin "1") (pinfunction "1_1") (pintype "passive"))
    )
    (net (code "31") (name "Net-(PAD6-P)") (class "Default")
      (node (ref "PAD6") (pin "1") (pinfunction "P_1") (pintype "passive"))
      (node (ref "R15") (pin "1") (pinfunction "1_1") (pintype "passive"))
    )
    (net (code "32") (name "Net-(PAD8-P)") (class "Default")
      (node (ref "PAD8") (pin "1") (pinfunction "P_1") (pintype "passive"))
      (node (ref "R16") (pin "1") (pinfunction "1_1") (pintype "passive"))
    )
    (net (code "33") (name "Net-(PAD10-P)") (class "Default")
      (node (ref "PAD10") (pin "1") (pinfunction "P_1") (pintype "passive"))
      (node (ref "R1") (pin "1") (pinfunction "1_1") (pintype "passive"))
    )
    (net (code "34") (name "Net-(PAD12-P)") (class "Default")
      (node (ref "PAD12") (pin "1") (pinfunction "P_1") (pintype "passive"))
      (node (ref "R8") (pin "1") (pinfunction "1_1") (pintype "passive"))
    )
    (net (code "35") (name "Net-(PAD13-P)") (class "Default")
      (node (ref "PAD13") (pin "1") (pinfunction "P_1") (pintype "passive"))
      (node (ref "R13") (pin "1") (pinfunction "1_1") (pintype "passive"))
    )
    (net (code "36") (name "Net-(PAD18-P)") (class "Default")
      (node (ref "JMP_4") (pin "1") (pinfunction "1_1") (pintype "passive"))
      (node (ref "JMP_4") (pin "2") (pinfunction "2_2") (pintype "passive"))
      (node (ref "PAD18") (pin "1") (pinfunction "P_1") (pintype "passive"))
      (node (ref "U1") (pin "4") (pinfunction "Y_4") (pintype "bidirectional"))
    )
    (net (code "37") (name "REC{slash}PB") (class "Default")
      (node (ref "PAD32") (pin "1") (pinfunction "P_1") (pintype "passive"))
      (node (ref "R6") (pin "2") (pinfunction "2_2") (pintype "passive"))
      (node (ref "S5") (pin "1") (pinfunction "1_1") (pintype "bidirectional"))
      (node (ref "U1") (pin "2") (pinfunction "A_2") (pintype "bidirectional"))
    )
    (net (code "38") (name "VCCIO") (class "Default")
      (node (ref "IC1") (pin "1") (pinfunction "1J_1") (pintype "bidirectional"))
      (node (ref "IC1") (pin "10") (pinfunction "~{2R}_10") (pintype "bidirectional"))
      (node (ref "IC1") (pin "11") (pinfunction "2K_11") (pintype "bidirectional"))
      (node (ref "IC1") (pin "13") (pinfunction "~{1R}_13") (pintype "bidirectional"))
      (node (ref "IC1") (pin "14") (pinfunction "VCC_14") (pintype "bidirectional"))
      (node (ref "IC1") (pin "4") (pinfunction "1K_4") (pintype "bidirectional"))
      (node (ref "IC1") (pin "8") (pinfunction "2J_8") (pintype "bidirectional"))
      (node (ref "IC2") (pin "1") (pinfunction "1J_1") (pintype "bidirectional"))
      (node (ref "IC2") (pin "10") (pinfunction "~{2R}_10") (pintype "bidirectional"))
      (node (ref "IC2") (pin "11") (pinfunction "2K_11") (pintype "bidirectional"))
      (node (ref "IC2") (pin "13") (pinfunction "~{1R}_13") (pintype "bidirectional"))
      (node (ref "IC2") (pin "14") (pinfunction "VCC_14") (pintype "bidirectional"))
      (node (ref "IC2") (pin "4") (pinfunction "1K_4") (pintype "bidirectional"))
      (node (ref "IC2") (pin "8") (pinfunction "2J_8") (pintype "bidirectional"))
      (node (ref "IC3") (pin "1") (pinfunction "1J_1") (pintype "bidirectional"))
      (node (ref "IC3") (pin "10") (pinfunction "~{2R}_10") (pintype "bidirectional"))
      (node (ref "IC3") (pin "11") (pinfunction "2K_11") (pintype "bidirectional"))
      (node (ref "IC3") (pin "13") (pinfunction "~{1R}_13") (pintype "bidirectional"))
      (node (ref "IC3") (pin "14") (pinfunction "VCC_14") (pintype "bidirectional"))
      (node (ref "IC3") (pin "4") (pinfunction "1K_4") (pintype "bidirectional"))
      (node (ref "IC3") (pin "8") (pinfunction "2J_8") (pintype "bidirectional"))
      (node (ref "IC4") (pin "1") (pinfunction "1J_1") (pintype "bidirectional"))
      (node (ref "IC4") (pin "10") (pinfunction "~{2R}_10") (pintype "bidirectional"))
      (node (ref "IC4") (pin "11") (pinfunction "2K_11") (pintype "bidirectional"))
      (node (ref "IC4") (pin "13") (pinfunction "~{1R}_13") (pintype "bidirectional"))
      (node (ref "IC4") (pin "14") (pinfunction "VCC_14") (pintype "bidirectional"))
      (node (ref "IC4") (pin "4") (pinfunction "1K_4") (pintype "bidirectional"))
      (node (ref "IC4") (pin "8") (pinfunction "2J_8") (pintype "bidirectional"))
      (node (ref "JMP_11") (pin "1") (pinfunction "1_1") (pintype "passive"))
      (node (ref "JMP_11") (pin "2") (pinfunction "2_2") (pintype "passive"))
      (node (ref "JMP_3") (pin "1") (pinfunction "1_1") (pintype "passive"))
      (node (ref "JMP_3") (pin "2") (pinfunction "2_2") (pintype "passive"))
      (node (ref "PAD17") (pin "1") (pinfunction "P_1") (pintype "passive"))
      (node (ref "PAD22") (pin "1") (pinfunction "P_1") (pintype "passive"))
      (node (ref "R11") (pin "2") (pinfunction "2_2") (pintype "passive"))
      (node (ref "R12") (pin "2") (pinfunction "2_2") (pintype "passive"))
      (node (ref "R14") (pin "2") (pinfunction "2_2") (pintype "passive"))
      (node (ref "R2") (pin "2") (pinfunction "2_2") (pintype "passive"))
      (node (ref "R4") (pin "2") (pinfunction "2_2") (pintype "passive"))
      (node (ref "R7") (pin "2") (pinfunction "2_2") (pintype "passive"))
      (node (ref "R9") (pin "2") (pinfunction "2_2") (pintype "passive"))
      (node (ref "S5") (pin "2") (pinfunction "2_2") (pintype "bidirectional"))
      (node (ref "U1") (pin "5") (pinfunction "VCC_5") (pintype "bidirectional"))
    )
    (net (code "39") (name "unconnected-(IC1-2Q-Pad5)") (class "Default")
      (node (ref "IC1") (pin "5") (pinfunction "2Q_5") (pintype "bidirectional"))
    )
    (net (code "40") (name "unconnected-(IC1-~{2CP}-Pad9)") (class "Default")
      (node (ref "IC1") (pin "9") (pinfunction "~{2CP}_9") (pintype "bidirectional"))
    )
    (net (code "41") (name "unconnected-(IC1-~{2Q}-Pad6)") (class "Default")
      (node (ref "IC1") (pin "6") (pinfunction "~{2Q}_6") (pintype "bidirectional"))
    )
    (net (code "42") (name "unconnected-(MP1-P$1-Pad1)") (class "Default")
      (node (ref "MP1") (pin "1") (pinfunction "P$1_1") (pintype "passive"))
    )
    (net (code "43") (name "unconnected-(MP2-P$1-Pad1)") (class "Default")
      (node (ref "MP2") (pin "1") (pinfunction "P$1_1") (pintype "passive"))
    )
    (net (code "44") (name "unconnected-(MP3-P$1-Pad1)") (class "Default")
      (node (ref "MP3") (pin "1") (pinfunction "P$1_1") (pintype "passive"))
    )
    (net (code "45") (name "unconnected-(MP4-P$1-Pad1)") (class "Default")
      (node (ref "MP4") (pin "1") (pinfunction "P$1_1") (pintype "passive"))
    )
    (net (code "46") (name "unconnected-(S1-PadMH1)") (class "Default")
      (node (ref "S1") (pin "MH1") (pinfunction "MH1_MH1") (pintype "bidirectional"))
    )
    (net (code "47") (name "unconnected-(S1-PadMH2)") (class "Default")
      (node (ref "S1") (pin "MH2") (pinfunction "MH2_MH2") (pintype "bidirectional"))
    )
    (net (code "48") (name "unconnected-(S2-PadMH1)") (class "Default")
      (node (ref "S2") (pin "MH1") (pinfunction "MH1_MH1") (pintype "bidirectional"))
    )
    (net (code "49") (name "unconnected-(S2-PadMH2)") (class "Default")
      (node (ref "S2") (pin "MH2") (pinfunction "MH2_MH2") (pintype "bidirectional"))
    )
    (net (code "50") (name "unconnected-(S4-PadMH1)") (class "Default")
      (node (ref "S4") (pin "MH1") (pinfunction "MH1_MH1") (pintype "bidirectional"))
    )
    (net (code "51") (name "unconnected-(S4-PadMH2)") (class "Default")
      (node (ref "S4") (pin "MH2") (pinfunction "MH2_MH2") (pintype "bidirectional"))
    )
    (net (code "52") (name "unconnected-(S5-PadMH1)") (class "Default")
      (node (ref "S5") (pin "MH1") (pinfunction "MH1_MH1") (pintype "bidirectional"))
    )
    (net (code "53") (name "unconnected-(S5-PadMH2)") (class "Default")
      (node (ref "S5") (pin "MH2") (pinfunction "MH2_MH2") (pintype "bidirectional"))
    )
    (net (code "54") (name "unconnected-(S6-PadMH1)") (class "Default")
      (node (ref "S6") (pin "MH1") (pinfunction "MH1_MH1") (pintype "bidirectional"))
    )
    (net (code "55") (name "unconnected-(S6-PadMH2)") (class "Default")
      (node (ref "S6") (pin "MH2") (pinfunction "MH2_MH2") (pintype "bidirectional"))
    )
    (net (code "56") (name "unconnected-(S7-PadMH1)") (class "Default")
      (node (ref "S7") (pin "MH1") (pinfunction "MH1_MH1") (pintype "bidirectional"))
    )
    (net (code "57") (name "unconnected-(S7-PadMH2)") (class "Default")
      (node (ref "S7") (pin "MH2") (pinfunction "MH2_MH2") (pintype "bidirectional"))
    )
    (net (code "58") (name "unconnected-(S8-PadMH1)") (class "Default")
      (node (ref "S8") (pin "MH1") (pinfunction "MH1_MH1") (pintype "bidirectional"))
    )
    (net (code "59") (name "unconnected-(S8-PadMH2)") (class "Default")
      (node (ref "S8") (pin "MH2") (pinfunction "MH2_MH2") (pintype "bidirectional"))
    )
    (net (code "60") (name "unconnected-(S9-PadMH1)") (class "Default")
      (node (ref "S9") (pin "MH1") (pinfunction "MH1_MH1") (pintype "bidirectional"))
    )
    (net (code "61") (name "unconnected-(S9-PadMH2)") (class "Default")
      (node (ref "S9") (pin "MH2") (pinfunction "MH2_MH2") (pintype "bidirectional"))
    )
    (net (code "62") (name "unconnected-(U1-NC-Pad1)") (class "Default")
      (node (ref "U1") (pin "1") (pinfunction "NC_1") (pintype "no_connect"))
    )
  )
)
